# DAC.net
KiCad netlist of a schematic drawn in Altium Designer
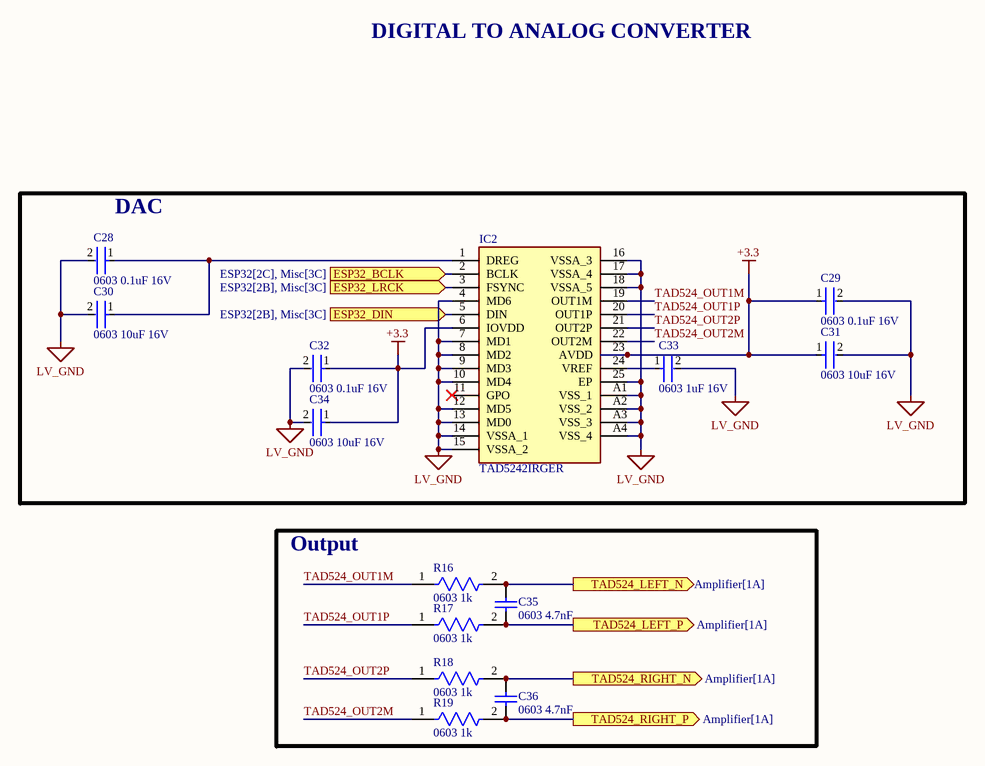
[diagram p0: DAC.SchDoc]

(export (version "E")
  (design (tool "Eeschema 10.0.6"))
  (components
    (comp (ref "C28")
      (value "0603 0.1uF 16V")
      (footprint "FP-CC0603-DA-MFG")
      (description "CAP CER 0.1UF 16V X7R 0603")
      (fields
        (field (name "OCTOPART") "https://octopart.com/cc0603krx7r7bb104-yageo-192941")
        (field (name "TOLERANCE") "0.1")
      )
      (libsource (lib "Altium Content Vault") (part "11868f565c42a9108669ba33697ecf6"))
    )
    (comp (ref "C29")
      (value "0603 0.1uF 16V")
      (footprint "FP-CC0603-DA-MFG")
      (description "CAP CER 0.1UF 16V X7R 0603")
      (fields
        (field (name "OCTOPART") "https://octopart.com/cc0603krx7r7bb104-yageo-192941")
        (field (name "TOLERANCE") "0.1")
      )
      (libsource (lib "Altium Content Vault") (part "11868f565c42a9108669ba33697ecf6"))
    )
    (comp (ref "C30")
      (value "0603 10uF 16V")
      (footprint "FP-0603-L_1_6_0_2-W_0_8_0-MFG")
      (description "Multilayer Ceramic Capacitor 10uF 16V X5R 20% SMD 0603 T/R")
      (fields (field (name "TOLERANCE") "20%"))
      (libsource (lib "Altium Content Vault") (part "b4654b650e69147ec39a6b967a45e02"))
    )
    (comp (ref "C31")
      (value "0603 10uF 16V")
      (footprint "FP-0603-L_1_6_0_2-W_0_8_0-MFG")
      (description "Multilayer Ceramic Capacitor 10uF 16V X5R 20% SMD 0603 T/R")
      (fields (field (name "TOLERANCE") "20%"))
      (libsource (lib "Altium Content Vault") (part "b4654b650e69147ec39a6b967a45e02"))
    )
    (comp (ref "C32")
      (value "0603 0.1uF 16V")
      (footprint "FP-CC0603-DA-MFG")
      (description "CAP CER 0.1UF 16V X7R 0603")
      (fields
        (field (name "OCTOPART") "https://octopart.com/cc0603krx7r7bb104-yageo-192941")
        (field (name "TOLERANCE") "0.1")
      )
      (libsource (lib "Altium Content Vault") (part "11868f565c42a9108669ba33697ecf6"))
    )
    (comp (ref "C33")
      (value "0603 1uF 16V")
      (footprint "FP-CC0603-DA-MFG")
      (description "CAP CER 1UF 16V X7R 0603")
      (fields (field (name "TOLERANCE") "0.1") (field (name "MANUFACTURER") "YAGEO"))
      (libsource (lib "Altium Content Vault") (part "11868f565c42a9108669ba33697ecf6"))
    )
    (comp (ref "C34")
      (value "0603 10uF 16V")
      (footprint "FP-0603-L_1_6_0_2-W_0_8_0-MFG")
      (description "Multilayer Ceramic Capacitor 10uF 16V X5R 20% SMD 0603 T/R")
      (fields (field (name "TOLERANCE") "20%"))
      (libsource (lib "Altium Content Vault") (part "b4654b650e69147ec39a6b967a45e02"))
    )
    (comp (ref "C35")
      (value "0603 4.7nF")
      (footprint "CAPC1608X90X35ML10T15")
      (fields (field (name "PART NUMBER") "GRM188R71H472KA01D") (field (name "MANUFACTURER") "Murata"))
      (libsource (lib "Altium Content Vault") (part "CAP"))
    )
    (comp (ref "C36")
      (value "0603 4.7nF")
      (footprint "CAPC1608X90X35ML10T15")
      (fields (field (name "PART NUMBER") "GRM188R71H472KA01D") (field (name "MANUFACTURER") "Murata"))
      (libsource (lib "Altium Content Vault") (part "CAP"))
    )
    (comp (ref "IC2")
      (value "TAD5242IRGER")
      (footprint "SamacSys:TAD5242IRGER")
      (description "Integrated Circuit")
      (fields (field (name "MOUSER PART NUMBER") "595-TAD5242IRGER"))
      (libsource (lib "*") (part "TAD5242IRGER"))
    )
    (comp (ref "R16")
      (value "0603 1k")
      (footprint "FP-AC0603-IPC_B")
      (description "RES 1kΩ 1.00% 0.1W 0603")
      (fields (field (name "TOLERANCE") "1%"))
      (libsource (lib "Altium Content Vault") (part "1029c3af85768c4190bb7ad29bc67b5"))
    )
    (comp (ref "R17")
      (value "0603 1k")
      (footprint "FP-AC0603-IPC_B")
      (description "RES 1kΩ 1.00% 0.1W 0603")
      (fields (field (name "TOLERANCE") "1%"))
      (libsource (lib "Altium Content Vault") (part "1029c3af85768c4190bb7ad29bc67b5"))
    )
    (comp (ref "R18")
      (value "0603 1k")
      (footprint "FP-AC0603-IPC_B")
      (description "RES 1kΩ 1.00% 0.1W 0603")
      (fields (field (name "TOLERANCE") "1%"))
      (libsource (lib "Altium Content Vault") (part "1029c3af85768c4190bb7ad29bc67b5"))
    )
    (comp (ref "R19")
      (value "0603 1k")
      (footprint "FP-AC0603-IPC_B")
      (description "RES 1kΩ 1.00% 0.1W 0603")
      (fields (field (name "TOLERANCE") "1%"))
      (libsource (lib "Altium Content Vault") (part "1029c3af85768c4190bb7ad29bc67b5"))
    )
  )
  (nets
    (net (code "1") (name "+3.3") (class "Default")
      (node (ref "C29") (pin "1") (pinfunction "1_1") (pintype "passive"))
      (node (ref "C31") (pin "1") (pinfunction "1_1") (pintype "passive"))
      (node (ref "C32") (pin "1") (pinfunction "1_1") (pintype "passive"))
      (node (ref "C34") (pin "1") (pinfunction "1_1") (pintype "passive"))
      (node (ref "IC2") (pin "23") (pinfunction "AVDD_23") (pintype "passive"))
      (node (ref "IC2") (pin "6") (pinfunction "IOVDD_6") (pintype "passive"))
    )
    (net (code "2") (name "/ESP32_BCLK") (class "Default")
      (node (ref "IC2") (pin "2") (pinfunction "BCLK_2") (pintype "passive"))
    )
    (net (code "3") (name "/ESP32_DIN") (class "Default")
      (node (ref "IC2") (pin "5") (pinfunction "DIN_5") (pintype "passive"))
    )
    (net (code "4") (name "/ESP32_LRCK") (class "Default")
      (node (ref "IC2") (pin "3") (pinfunction "FSYNC_3") (pintype "passive"))
    )
    (net (code "5") (name "/TAD524_LEFT_N") (class "Default")
      (node (ref "C35") (pin "1") (pinfunction "1_1") (pintype "passive"))
      (node (ref "R16") (pin "2") (pinfunction "2_2") (pintype "passive"))
    )
    (net (code "6") (name "/TAD524_LEFT_P") (class "Default")
      (node (ref "C35") (pin "2") (pinfunction "2_2") (pintype "passive"))
      (node (ref "R17") (pin "2") (pinfunction "2_2") (pintype "passive"))
    )
    (net (code "7") (name "/TAD524_OUT1M") (class "Default")
      (node (ref "IC2") (pin "19") (pinfunction "OUT1M_19") (pintype "passive"))
      (node (ref "R16") (pin "1") (pinfunction "1_1") (pintype "passive"))
    )
    (net (code "8") (name "/TAD524_OUT1P") (class "Default")
      (node (ref "IC2") (pin "20") (pinfunction "OUT1P_20") (pintype "passive"))
      (node (ref "R17") (pin "1") (pinfunction "1_1") (pintype "passive"))
    )
    (net (code "9") (name "/TAD524_OUT2M") (class "Default")
      (node (ref "IC2") (pin "22") (pinfunction "OUT2M_22") (pintype "passive"))
      (node (ref "R19") (pin "1") (pinfunction "1_1") (pintype "passive"))
    )
    (net (code "10") (name "/TAD524_OUT2P") (class "Default")
      (node (ref "IC2") (pin "21") (pinfunction "OUT2P_21") (pintype "passive"))
      (node (ref "R18") (pin "1") (pinfunction "1_1") (pintype "passive"))
    )
    (net (code "11") (name "/TAD524_RIGHT_N") (class "Default")
      (node (ref "C36") (pin "1") (pinfunction "1_1") (pintype "passive"))
      (node (ref "R18") (pin "2") (pinfunction "2_2") (pintype "passive"))
    )
    (net (code "12") (name "/TAD524_RIGHT_P") (class "Default")
      (node (ref "C36") (pin "2") (pinfunction "2_2") (pintype "passive"))
      (node (ref "R19") (pin "2") (pinfunction "2_2") (pintype "passive"))
    )
    (net (code "13") (name "LV_GND") (class "Default")
      (node (ref "C28") (pin "2") (pinfunction "2_2") (pintype "passive"))
      (node (ref "C29") (pin "2") (pinfunction "2_2") (pintype "passive"))
      (node (ref "C30") (pin "2") (pinfunction "2_2") (pintype "passive"))
      (node (ref "C31") (pin "2") (pinfunction "2_2") (pintype "passive"))
      (node (ref "C32") (pin "2") (pinfunction "2_2") (pintype "passive"))
      (node (ref "C33") (pin "2") (pinfunction "2_2") (pintype "passive"))
      (node (ref "C34") (pin "2") (pinfunction "2_2") (pintype "passive"))
      (node (ref "IC2") (pin "10") (pinfunction "MD4_10") (pintype "passive"))
      (node (ref "IC2") (pin "12") (pinfunction "MD5_12") (pintype "passive"))
      (node (ref "IC2") (pin "13") (pinfunction "MD0_13") (pintype "passive"))
      (node (ref "IC2") (pin "14") (pinfunction "VSSA_1_14") (pintype "passive"))
      (node (ref "IC2") (pin "15") (pinfunction "VSSA_2_15") (pintype "passive"))
      (node (ref "IC2") (pin "16") (pinfunction "VSSA_3_16") (pintype "passive"))
      (node (ref "IC2") (pin "17") (pinfunction "VSSA_4_17") (pintype "passive"))
      (node (ref "IC2") (pin "18") (pinfunction "VSSA_5_18") (pintype "passive"))
      (node (ref "IC2") (pin "25") (pinfunction "EP_25") (pintype "passive"))
      (node (ref "IC2") (pin "4") (pinfunction "MD6_4") (pintype "passive"))
      (node (ref "IC2") (pin "7") (pinfunction "MD1_7") (pintype "passive"))
      (node (ref "IC2") (pin "8") (pinfunction "MD2_8") (pintype "passive"))
      (node (ref "IC2") (pin "9") (pinfunction "MD3_9") (pintype "passive"))
      (node (ref "IC2") (pin "A1") (pinfunction "VSS_1_A1") (pintype "passive"))
      (node (ref "IC2") (pin "A2") (pinfunction "VSS_2_A2") (pintype "passive"))
      (node (ref "IC2") (pin "A3") (pinfunction "VSS_3_A3") (pintype "passive"))
      (node (ref "IC2") (pin "A4") (pinfunction "VSS_4_A4") (pintype "passive"))
    )
    (net (code "14") (name "Net-(IC2-DREG)") (class "Default")
      (node (ref "C28") (pin "1") (pinfunction "1_1") (pintype "passive"))
      (node (ref "C30") (pin "1") (pinfunction "1_1") (pintype "passive"))
      (node (ref "IC2") (pin "1") (pinfunction "DREG_1") (pintype "passive"))
    )
    (net (code "15") (name "Net-(IC2-VREF)") (class "Default")
      (node (ref "C33") (pin "1") (pinfunction "1_1") (pintype "passive"))
      (node (ref "IC2") (pin "24") (pinfunction "VREF_24") (pintype "passive"))
    )
    (net (code "16") (name "unconnected-(IC2-GPO-Pad11)") (class "Default")
      (node (ref "IC2") (pin "11") (pinfunction "GPO_11") (pintype "passive+no_connect"))
    )
  )
)
